# GiGaMega_nano.net
KiCad netlist of a schematic drawn in EAGLE
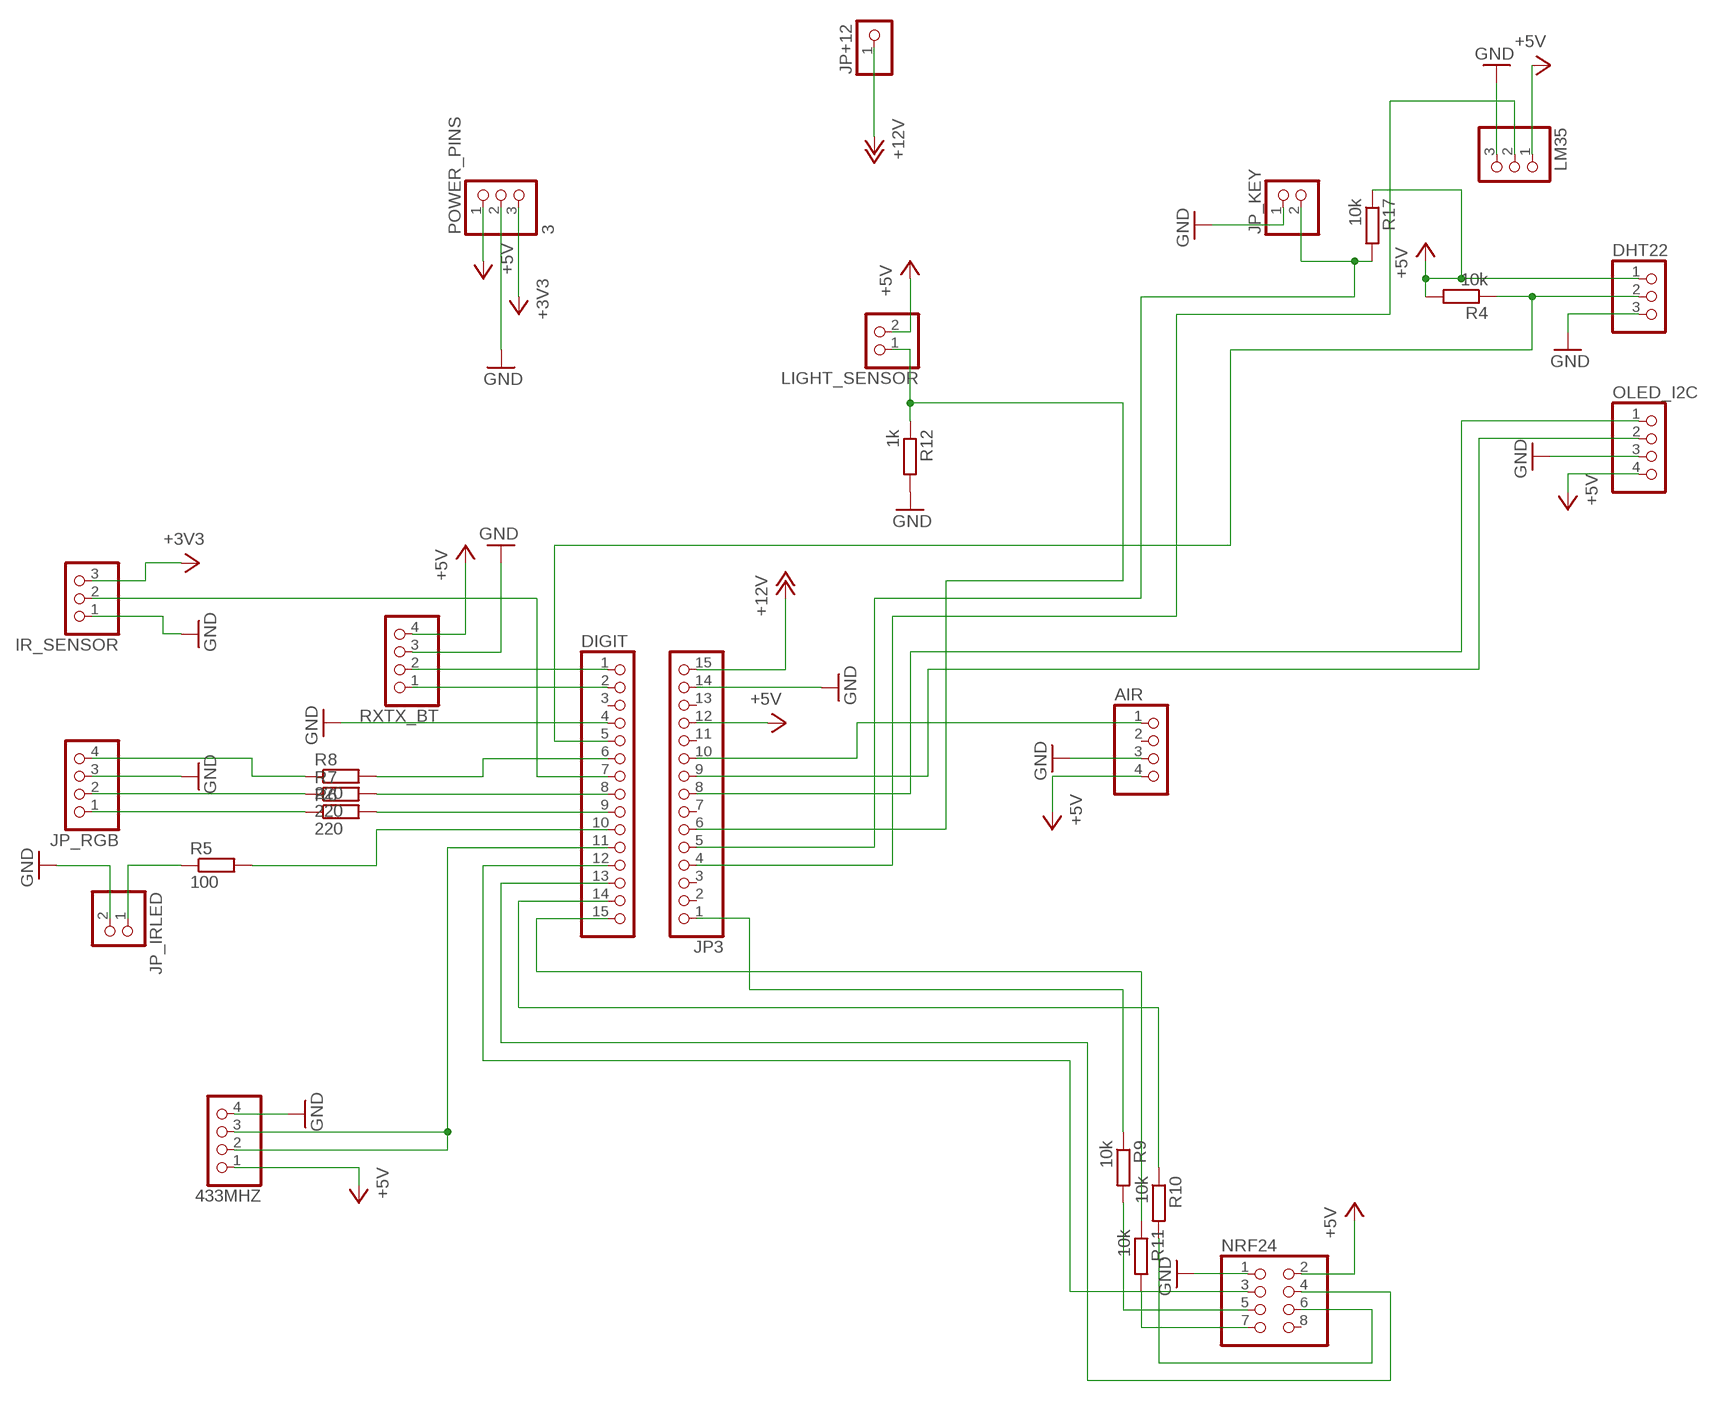
[diagram p0: schematic, sheet 1]

(export (version "E")
  (design (tool "Eeschema 10.0.6"))
  (components
    (comp (ref "433MHZ")
      (value "PINHD-1X4")
      (footprint "eagle-import:1X04")
      (libsource (lib "eagle-import") (part "PINHD-1X4"))
    )
    (comp (ref "AIR")
      (value "PINHD-1X4")
      (footprint "eagle-import:1X04")
      (libsource (lib "eagle-import") (part "PINHD-1X4"))
    )
    (comp (ref "DHT22")
      (value "PINHD-1X3")
      (footprint "eagle-import:1X03")
      (libsource (lib "eagle-import") (part "PINHD-1X3"))
    )
    (comp (ref "DIGIT")
      (value "PINHD-1X15")
      (footprint "eagle-import:1X15")
      (libsource (lib "eagle-import") (part "PINHD-1X15"))
    )
    (comp (ref "IR_SENSOR")
      (value "PINHD-1X3")
      (footprint "eagle-import:1X03")
      (libsource (lib "eagle-import") (part "PINHD-1X3"))
    )
    (comp (ref "JP+12")
      (value "PINHD-1X1")
      (footprint "eagle-import:1X01")
      (libsource (lib "eagle-import") (part "PINHD-1X1"))
    )
    (comp (ref "JP3")
      (value "PINHD-1X15")
      (footprint "eagle-import:1X15")
      (libsource (lib "eagle-import") (part "PINHD-1X15"))
    )
    (comp (ref "JP_IRLED")
      (value "PINHD-1X2")
      (footprint "eagle-import:1X02")
      (libsource (lib "eagle-import") (part "PINHD-1X2"))
    )
    (comp (ref "JP_KEY")
      (value "PINHD-1X2")
      (footprint "eagle-import:1X02")
      (libsource (lib "eagle-import") (part "PINHD-1X2"))
    )
    (comp (ref "JP_RGB")
      (value "PINHD-1X4")
      (footprint "eagle-import:1X04")
      (libsource (lib "eagle-import") (part "PINHD-1X4"))
    )
    (comp (ref "LIGHT_SENSOR")
      (value "PINHD-1X2")
      (footprint "eagle-import:1X02")
      (libsource (lib "eagle-import") (part "PINHD-1X2"))
    )
    (comp (ref "LM35")
      (value "PINHD-1X3")
      (footprint "eagle-import:1X03")
      (libsource (lib "eagle-import") (part "PINHD-1X3"))
    )
    (comp (ref "NRF24")
      (value "PINHD-2X4")
      (footprint "eagle-import:2X04")
      (libsource (lib "eagle-import") (part "PINHD-2X4"))
    )
    (comp (ref "OLED_I2C")
      (value "PINHD-1X4")
      (footprint "eagle-import:1X04")
      (libsource (lib "eagle-import") (part "PINHD-1X4"))
    )
    (comp (ref "POWER_PINS")
      (value "3")
      (footprint "eagle-import:1X03")
      (libsource (lib "eagle-import") (part "PINHD-1X3"))
    )
    (comp (ref "R4")
      (value "10k")
      (footprint "eagle-import:R1206")
      (libsource (lib "eagle-import") (part "R-EU_R1206"))
    )
    (comp (ref "R5")
      (value "100")
      (footprint "eagle-import:R1206")
      (libsource (lib "eagle-import") (part "R-EU_R1206"))
    )
    (comp (ref "R6")
      (value "220")
      (footprint "eagle-import:R1206")
      (libsource (lib "eagle-import") (part "R-EU_R1206"))
    )
    (comp (ref "R7")
      (value "220")
      (footprint "eagle-import:R1206")
      (libsource (lib "eagle-import") (part "R-EU_R1206"))
    )
    (comp (ref "R8")
      (value "220")
      (footprint "eagle-import:R1206")
      (libsource (lib "eagle-import") (part "R-EU_R1206"))
    )
    (comp (ref "R9")
      (value "10k")
      (footprint "eagle-import:R1206")
      (libsource (lib "eagle-import") (part "R-EU_R1206"))
    )
    (comp (ref "R10")
      (value "10k")
      (footprint "eagle-import:R1206")
      (libsource (lib "eagle-import") (part "R-EU_R1206"))
    )
    (comp (ref "R11")
      (value "10k")
      (footprint "eagle-import:R1206")
      (libsource (lib "eagle-import") (part "R-EU_R1206"))
    )
    (comp (ref "R12")
      (value "1k")
      (footprint "eagle-import:R1206")
      (libsource (lib "eagle-import") (part "R-EU_R1206"))
    )
    (comp (ref "R17")
      (value "10k")
      (footprint "eagle-import:R1206")
      (libsource (lib "eagle-import") (part "R-EU_R1206"))
    )
    (comp (ref "RXTX_BT")
      (value "PINHD-1X4")
      (footprint "eagle-import:1X04")
      (libsource (lib "eagle-import") (part "PINHD-1X4"))
    )
  )
  (nets
    (net (code "1") (name "+3V3") (class "Default")
      (node (ref "IR_SENSOR") (pin "3") (pinfunction "3_3") (pintype "passive"))
      (node (ref "POWER_PINS") (pin "3") (pinfunction "3_3") (pintype "passive"))
    )
    (net (code "2") (name "+5V") (class "Default")
      (node (ref "433MHZ") (pin "1") (pinfunction "1_1") (pintype "passive"))
      (node (ref "AIR") (pin "4") (pinfunction "4_4") (pintype "passive"))
      (node (ref "DHT22") (pin "1") (pinfunction "1_1") (pintype "passive"))
      (node (ref "JP3") (pin "12") (pinfunction "12_12") (pintype "passive"))
      (node (ref "LIGHT_SENSOR") (pin "2") (pinfunction "2_2") (pintype "passive"))
      (node (ref "LM35") (pin "1") (pinfunction "1_1") (pintype "passive"))
      (node (ref "NRF24") (pin "2") (pinfunction "2_2") (pintype "passive"))
      (node (ref "OLED_I2C") (pin "4") (pinfunction "4_4") (pintype "passive"))
      (node (ref "POWER_PINS") (pin "1") (pinfunction "1_1") (pintype "passive"))
      (node (ref "R17") (pin "1") (pinfunction "1_1") (pintype "passive"))
      (node (ref "R4") (pin "2") (pinfunction "2_2") (pintype "passive"))
      (node (ref "RXTX_BT") (pin "4") (pinfunction "4_4") (pintype "passive"))
    )
    (net (code "3") (name "+12V") (class "Default")
      (node (ref "JP+12") (pin "1") (pinfunction "1_1") (pintype "passive"))
      (node (ref "JP3") (pin "15") (pinfunction "15_15") (pintype "passive"))
    )
    (net (code "4") (name "GND") (class "Default")
      (node (ref "433MHZ") (pin "4") (pinfunction "4_4") (pintype "passive"))
      (node (ref "AIR") (pin "3") (pinfunction "3_3") (pintype "passive"))
      (node (ref "DHT22") (pin "3") (pinfunction "3_3") (pintype "passive"))
      (node (ref "DIGIT") (pin "4") (pinfunction "4_4") (pintype "passive"))
      (node (ref "IR_SENSOR") (pin "1") (pinfunction "1_1") (pintype "passive"))
      (node (ref "JP3") (pin "14") (pinfunction "14_14") (pintype "passive"))
      (node (ref "JP_IRLED") (pin "2") (pinfunction "2_2") (pintype "passive"))
      (node (ref "JP_KEY") (pin "1") (pinfunction "1_1") (pintype "passive"))
      (node (ref "JP_RGB") (pin "3") (pinfunction "3_3") (pintype "passive"))
      (node (ref "LM35") (pin "3") (pinfunction "3_3") (pintype "passive"))
      (node (ref "NRF24") (pin "1") (pinfunction "1_1") (pintype "passive"))
      (node (ref "OLED_I2C") (pin "3") (pinfunction "3_3") (pintype "passive"))
      (node (ref "POWER_PINS") (pin "2") (pinfunction "2_2") (pintype "passive"))
      (node (ref "R12") (pin "2") (pinfunction "2_2") (pintype "passive"))
      (node (ref "RXTX_BT") (pin "3") (pinfunction "3_3") (pintype "passive"))
    )
    (net (code "5") (name "Net-(433MHZ-Pad2)") (class "Default")
      (node (ref "433MHZ") (pin "2") (pinfunction "2_2") (pintype "passive"))
      (node (ref "433MHZ") (pin "3") (pinfunction "3_3") (pintype "passive"))
      (node (ref "DIGIT") (pin "11") (pinfunction "11_11") (pintype "passive"))
    )
    (net (code "6") (name "Net-(AIR-Pad1)") (class "Default")
      (node (ref "AIR") (pin "1") (pinfunction "1_1") (pintype "passive"))
      (node (ref "JP3") (pin "10") (pinfunction "10_10") (pintype "passive"))
    )
    (net (code "7") (name "Net-(DHT22-Pad2)") (class "Default")
      (node (ref "DHT22") (pin "2") (pinfunction "2_2") (pintype "passive"))
      (node (ref "DIGIT") (pin "5") (pinfunction "5_5") (pintype "passive"))
      (node (ref "R4") (pin "1") (pinfunction "1_1") (pintype "passive"))
    )
    (net (code "8") (name "Net-(DIGIT-Pad1)") (class "Default")
      (node (ref "DIGIT") (pin "1") (pinfunction "1_1") (pintype "passive"))
      (node (ref "RXTX_BT") (pin "2") (pinfunction "2_2") (pintype "passive"))
    )
    (net (code "9") (name "Net-(DIGIT-Pad2)") (class "Default")
      (node (ref "DIGIT") (pin "2") (pinfunction "2_2") (pintype "passive"))
      (node (ref "RXTX_BT") (pin "1") (pinfunction "1_1") (pintype "passive"))
    )
    (net (code "10") (name "Net-(DIGIT-Pad6)") (class "Default")
      (node (ref "DIGIT") (pin "6") (pinfunction "6_6") (pintype "passive"))
      (node (ref "R8") (pin "2") (pinfunction "2_2") (pintype "passive"))
    )
    (net (code "11") (name "Net-(DIGIT-Pad7)") (class "Default")
      (node (ref "DIGIT") (pin "7") (pinfunction "7_7") (pintype "passive"))
      (node (ref "IR_SENSOR") (pin "2") (pinfunction "2_2") (pintype "passive"))
    )
    (net (code "12") (name "Net-(DIGIT-Pad8)") (class "Default")
      (node (ref "DIGIT") (pin "8") (pinfunction "8_8") (pintype "passive"))
      (node (ref "R7") (pin "2") (pinfunction "2_2") (pintype "passive"))
    )
    (net (code "13") (name "Net-(DIGIT-Pad9)") (class "Default")
      (node (ref "DIGIT") (pin "9") (pinfunction "9_9") (pintype "passive"))
      (node (ref "R6") (pin "2") (pinfunction "2_2") (pintype "passive"))
    )
    (net (code "14") (name "Net-(DIGIT-Pad10)") (class "Default")
      (node (ref "DIGIT") (pin "10") (pinfunction "10_10") (pintype "passive"))
      (node (ref "R5") (pin "2") (pinfunction "2_2") (pintype "passive"))
    )
    (net (code "15") (name "Net-(DIGIT-Pad12)") (class "Default")
      (node (ref "DIGIT") (pin "12") (pinfunction "12_12") (pintype "passive"))
      (node (ref "NRF24") (pin "3") (pinfunction "3_3") (pintype "passive"))
    )
    (net (code "16") (name "Net-(DIGIT-Pad13)") (class "Default")
      (node (ref "DIGIT") (pin "13") (pinfunction "13_13") (pintype "passive"))
      (node (ref "NRF24") (pin "4") (pinfunction "4_4") (pintype "passive"))
    )
    (net (code "17") (name "Net-(DIGIT-Pad14)") (class "Default")
      (node (ref "DIGIT") (pin "14") (pinfunction "14_14") (pintype "passive"))
      (node (ref "R10") (pin "1") (pinfunction "1_1") (pintype "passive"))
    )
    (net (code "18") (name "Net-(DIGIT-Pad15)") (class "Default")
      (node (ref "DIGIT") (pin "15") (pinfunction "15_15") (pintype "passive"))
      (node (ref "R11") (pin "1") (pinfunction "1_1") (pintype "passive"))
    )
    (net (code "19") (name "Net-(JP3-Pad1)") (class "Default")
      (node (ref "JP3") (pin "1") (pinfunction "1_1") (pintype "passive"))
      (node (ref "R9") (pin "1") (pinfunction "1_1") (pintype "passive"))
    )
    (net (code "20") (name "Net-(JP3-Pad4)") (class "Default")
      (node (ref "JP3") (pin "4") (pinfunction "4_4") (pintype "passive"))
      (node (ref "LM35") (pin "2") (pinfunction "2_2") (pintype "passive"))
    )
    (net (code "21") (name "Net-(JP3-Pad5)") (class "Default")
      (node (ref "JP3") (pin "5") (pinfunction "5_5") (pintype "passive"))
      (node (ref "JP_KEY") (pin "2") (pinfunction "2_2") (pintype "passive"))
      (node (ref "R17") (pin "2") (pinfunction "2_2") (pintype "passive"))
    )
    (net (code "22") (name "Net-(JP3-Pad6)") (class "Default")
      (node (ref "JP3") (pin "6") (pinfunction "6_6") (pintype "passive"))
      (node (ref "LIGHT_SENSOR") (pin "1") (pinfunction "1_1") (pintype "passive"))
      (node (ref "R12") (pin "1") (pinfunction "1_1") (pintype "passive"))
    )
    (net (code "23") (name "Net-(JP3-Pad8)") (class "Default")
      (node (ref "JP3") (pin "8") (pinfunction "8_8") (pintype "passive"))
      (node (ref "OLED_I2C") (pin "1") (pinfunction "1_1") (pintype "passive"))
    )
    (net (code "24") (name "Net-(JP3-Pad9)") (class "Default")
      (node (ref "JP3") (pin "9") (pinfunction "9_9") (pintype "passive"))
      (node (ref "OLED_I2C") (pin "2") (pinfunction "2_2") (pintype "passive"))
    )
    (net (code "25") (name "Net-(JP_IRLED-Pad1)") (class "Default")
      (node (ref "JP_IRLED") (pin "1") (pinfunction "1_1") (pintype "passive"))
      (node (ref "R5") (pin "1") (pinfunction "1_1") (pintype "passive"))
    )
    (net (code "26") (name "Net-(JP_RGB-Pad1)") (class "Default")
      (node (ref "JP_RGB") (pin "1") (pinfunction "1_1") (pintype "passive"))
      (node (ref "R6") (pin "1") (pinfunction "1_1") (pintype "passive"))
    )
    (net (code "27") (name "Net-(JP_RGB-Pad2)") (class "Default")
      (node (ref "JP_RGB") (pin "2") (pinfunction "2_2") (pintype "passive"))
      (node (ref "R7") (pin "1") (pinfunction "1_1") (pintype "passive"))
    )
    (net (code "28") (name "Net-(JP_RGB-Pad4)") (class "Default")
      (node (ref "JP_RGB") (pin "4") (pinfunction "4_4") (pintype "passive"))
      (node (ref "R8") (pin "1") (pinfunction "1_1") (pintype "passive"))
    )
    (net (code "29") (name "Net-(NRF24-Pad5)") (class "Default")
      (node (ref "NRF24") (pin "5") (pinfunction "5_5") (pintype "passive"))
      (node (ref "R9") (pin "2") (pinfunction "2_2") (pintype "passive"))
    )
    (net (code "30") (name "Net-(NRF24-Pad6)") (class "Default")
      (node (ref "NRF24") (pin "6") (pinfunction "6_6") (pintype "passive"))
      (node (ref "R10") (pin "2") (pinfunction "2_2") (pintype "passive"))
    )
    (net (code "31") (name "Net-(NRF24-Pad7)") (class "Default")
      (node (ref "NRF24") (pin "7") (pinfunction "7_7") (pintype "passive"))
      (node (ref "R11") (pin "2") (pinfunction "2_2") (pintype "passive"))
    )
    (net (code "32") (name "unconnected-(AIR-Pad2)") (class "Default")
      (node (ref "AIR") (pin "2") (pinfunction "2_2") (pintype "passive"))
    )
    (net (code "33") (name "unconnected-(DIGIT-Pad3)") (class "Default")
      (node (ref "DIGIT") (pin "3") (pinfunction "3_3") (pintype "passive"))
    )
    (net (code "34") (name "unconnected-(JP3-Pad2)") (class "Default")
      (node (ref "JP3") (pin "2") (pinfunction "2_2") (pintype "passive"))
    )
    (net (code "35") (name "unconnected-(JP3-Pad3)") (class "Default")
      (node (ref "JP3") (pin "3") (pinfunction "3_3") (pintype "passive"))
    )
    (net (code "36") (name "unconnected-(JP3-Pad7)") (class "Default")
      (node (ref "JP3") (pin "7") (pinfunction "7_7") (pintype "passive"))
    )
    (net (code "37") (name "unconnected-(JP3-Pad11)") (class "Default")
      (node (ref "JP3") (pin "11") (pinfunction "11_11") (pintype "passive"))
    )
    (net (code "38") (name "unconnected-(JP3-Pad13)") (class "Default")
      (node (ref "JP3") (pin "13") (pinfunction "13_13") (pintype "passive"))
    )
    (net (code "39") (name "unconnected-(NRF24-Pad8)") (class "Default")
      (node (ref "NRF24") (pin "8") (pinfunction "8_8") (pintype "passive"))
    )
  )
)
